# PIC32MZ.net
KiCad netlist of a schematic drawn in Altium Designer
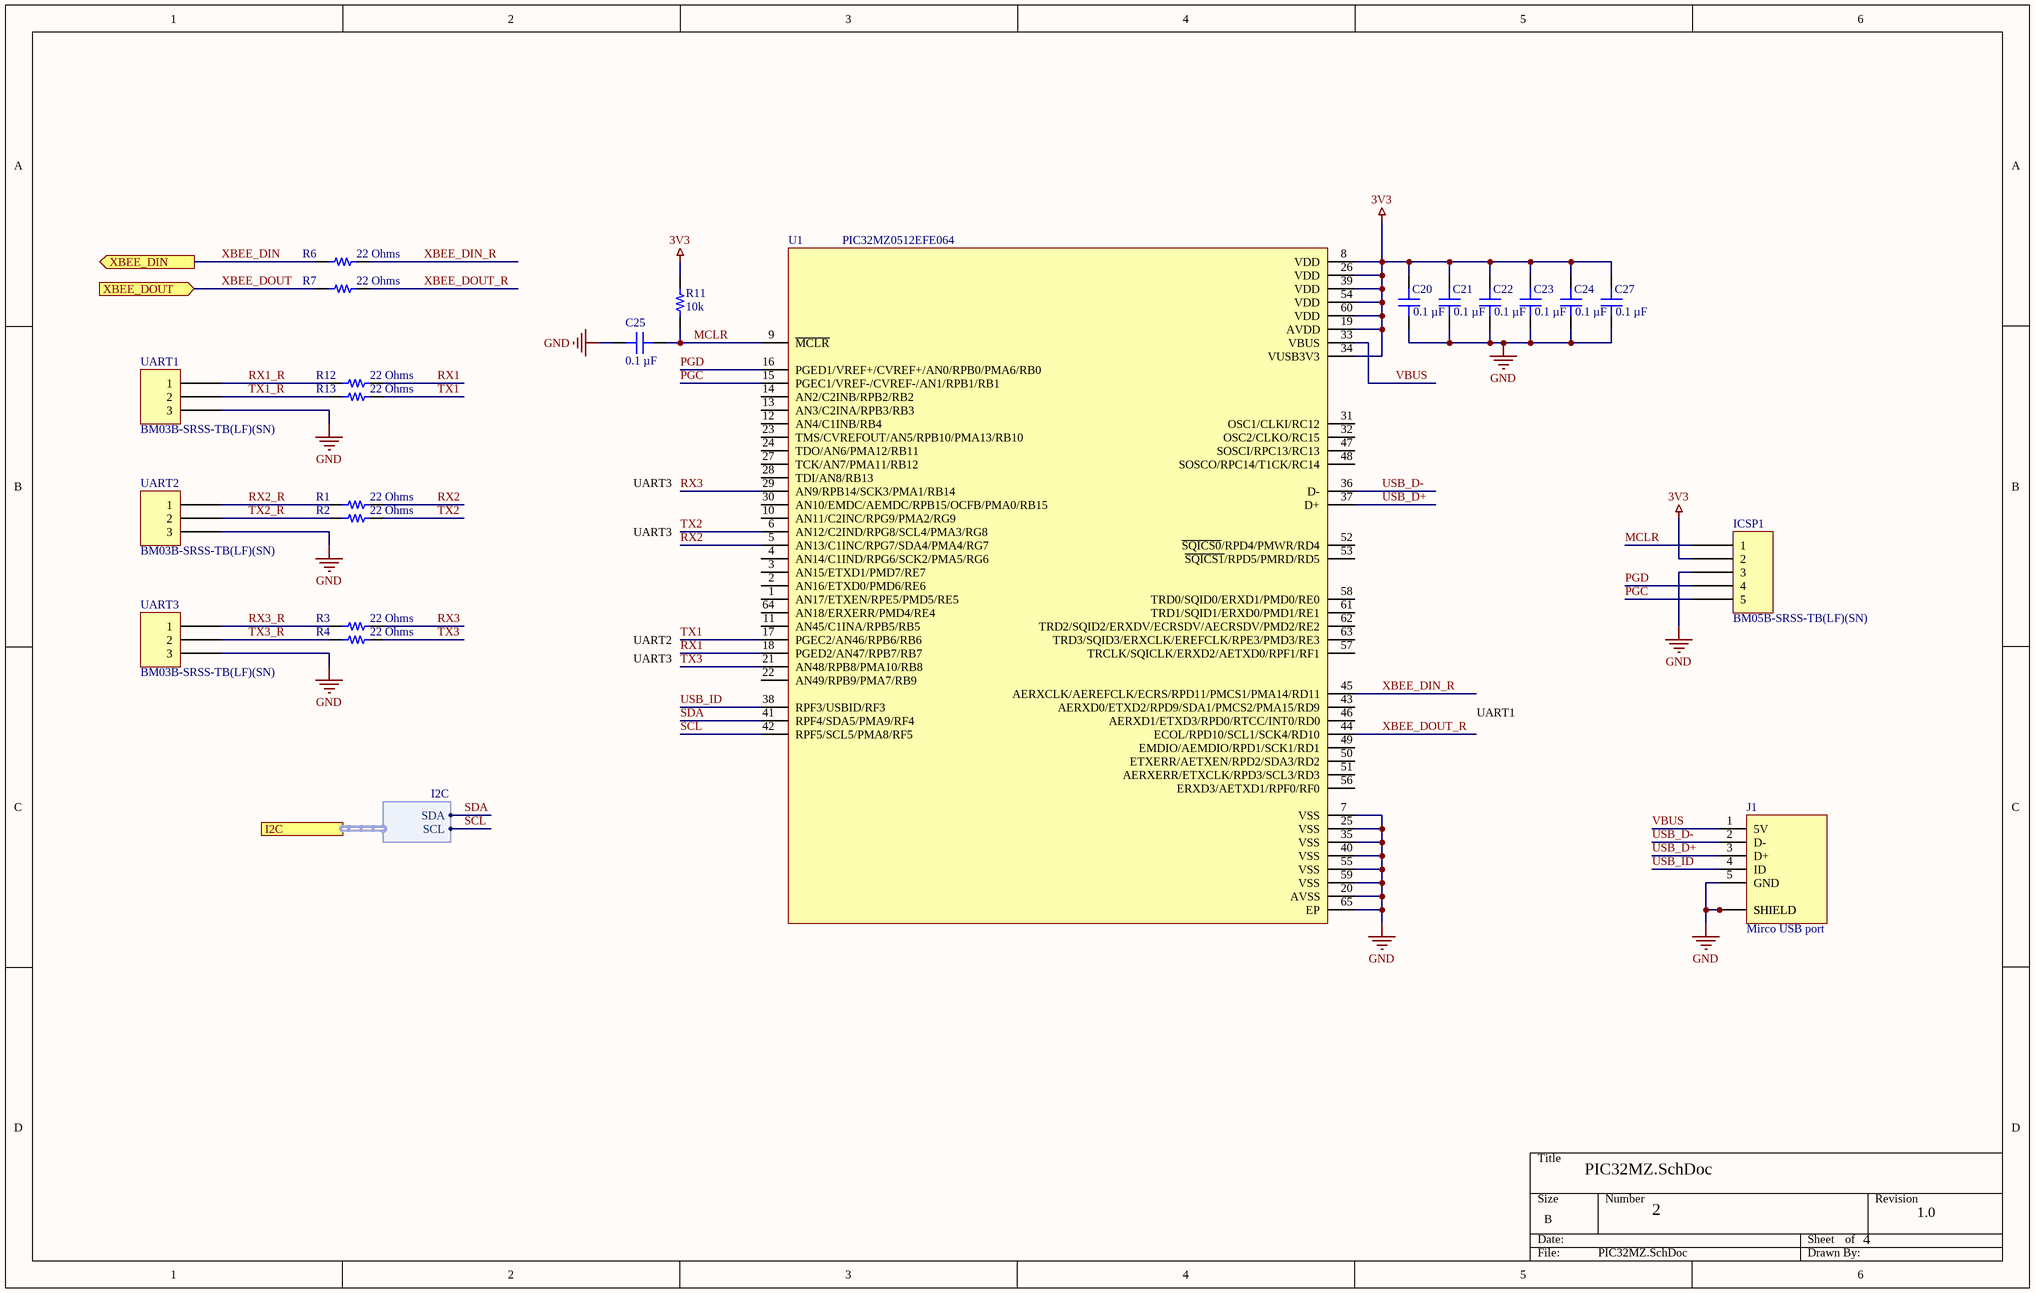
[diagram p0: PIC32MZ.SchDoc]

(export (version "E")
  (design (tool "Eeschema 10.0.6"))
  (components
    (comp (ref "C20")
      (value "0.1 µF")
      (footprint "CAP 0402_1005")
      (description "CAP CER 0.1UF 16V X7R 0402")
      (fields (field (name "PART NUMBER") "C0402C104K4RACAUTO") (field (name "MANUFACTURER") "KEMET"))
      (libsource (lib "Celestial Altium Library - altium_library") (part "Capacitor"))
    )
    (comp (ref "C21")
      (value "0.1 µF")
      (footprint "CAP 0402_1005")
      (description "CAP CER 0.1UF 16V X7R 0402")
      (fields (field (name "PART NUMBER") "C0402C104K4RACAUTO") (field (name "MANUFACTURER") "KEMET"))
      (libsource (lib "Celestial Altium Library - altium_library") (part "Capacitor"))
    )
    (comp (ref "C22")
      (value "0.1 µF")
      (footprint "CAP 0402_1005")
      (description "CAP CER 0.1UF 16V X7R 0402")
      (fields (field (name "PART NUMBER") "C0402C104K4RACAUTO") (field (name "MANUFACTURER") "KEMET"))
      (libsource (lib "Celestial Altium Library - altium_library") (part "Capacitor"))
    )
    (comp (ref "C23")
      (value "0.1 µF")
      (footprint "CAP 0402_1005")
      (description "CAP CER 0.1UF 16V X7R 0402")
      (fields (field (name "PART NUMBER") "C0402C104K4RACAUTO") (field (name "MANUFACTURER") "KEMET"))
      (libsource (lib "Celestial Altium Library - altium_library") (part "Capacitor"))
    )
    (comp (ref "C24")
      (value "0.1 µF")
      (footprint "CAP 0402_1005")
      (description "CAP CER 0.1UF 16V X7R 0402")
      (fields (field (name "PART NUMBER") "C0402C104K4RACAUTO") (field (name "MANUFACTURER") "KEMET"))
      (libsource (lib "Celestial Altium Library - altium_library") (part "Capacitor"))
    )
    (comp (ref "C25")
      (value "0.1 µF")
      (footprint "CAP 0402_1005")
      (description "CAP CER 0.1UF 16V X7R 0402")
      (fields (field (name "PART NUMBER") "C0402C104K4RACAUTO") (field (name "MANUFACTURER") "KEMET"))
      (libsource (lib "Celestial Altium Library - altium_library") (part "Capacitor"))
    )
    (comp (ref "C27")
      (value "0.1 µF")
      (footprint "CAP 0402_1005")
      (description "CAP CER 0.1UF 16V X7R 0402")
      (fields (field (name "PART NUMBER") "C0402C104K4RACAUTO") (field (name "MANUFACTURER") "KEMET"))
      (libsource (lib "Celestial Altium Library - altium_library") (part "Capacitor"))
    )
    (comp (ref "ICSP1")
      (value "BM05B-SRSS-TB(LF)(SN)")
      (footprint "JST BM05B-SRSS-TB")
      (description "CONN HEADER SMD 5POS 1MM")
      (fields (field (name "MANUFACTURER") "JST Sales America Inc."))
      (libsource (lib "Celestial Altium Library - altium_library") (part "5 Pin"))
    )
    (comp (ref "J1")
      (value "Mirco USB port")
      (footprint "AMPHENOL_10118194-0001LF")
      (description "USB - micro B USB 2.0 Receptacle Connector 5 Position Surface Mount, Right Angle; Through Hole")
      (fields (field (name "MF") "Amphenol ICC") (field (name "MP") "10118194-0001LF"))
      (libsource (lib "IC") (part "10118194-0001LF"))
    )
    (comp (ref "R1")
      (value "22 Ohms")
      (footprint "RES 0402_1005")
      (description "RES 14.3K OHM 1% 1/10W 0402")
      (fields
        (field (name "PART NUMBER") "RK73H1ETTP1432F")
        (field (name "MANUFACTURER") "KOA Speer Electronics, Inc.")
      )
      (libsource (lib "Celestial Altium Library - altium_library") (part "Resistor"))
    )
    (comp (ref "R2")
      (value "22 Ohms")
      (footprint "RES 0402_1005")
      (description "RES 14.3K OHM 1% 1/10W 0402")
      (fields
        (field (name "PART NUMBER") "RK73H1ETTP1432F")
        (field (name "MANUFACTURER") "KOA Speer Electronics, Inc.")
      )
      (libsource (lib "Celestial Altium Library - altium_library") (part "Resistor"))
    )
    (comp (ref "R3")
      (value "22 Ohms")
      (footprint "RES 0402_1005")
      (description "RES 14.3K OHM 1% 1/10W 0402")
      (fields
        (field (name "PART NUMBER") "RK73H1ETTP1432F")
        (field (name "MANUFACTURER") "KOA Speer Electronics, Inc.")
      )
      (libsource (lib "Celestial Altium Library - altium_library") (part "Resistor"))
    )
    (comp (ref "R4")
      (value "22 Ohms")
      (footprint "RES 0402_1005")
      (description "RES 14.3K OHM 1% 1/10W 0402")
      (fields
        (field (name "PART NUMBER") "RK73H1ETTP1432F")
        (field (name "MANUFACTURER") "KOA Speer Electronics, Inc.")
      )
      (libsource (lib "Celestial Altium Library - altium_library") (part "Resistor"))
    )
    (comp (ref "R6")
      (value "22 Ohms")
      (footprint "RES 0402_1005")
      (description "RES 14.3K OHM 1% 1/10W 0402")
      (fields
        (field (name "PART NUMBER") "RK73H1ETTP1432F")
        (field (name "MANUFACTURER") "KOA Speer Electronics, Inc.")
      )
      (libsource (lib "Celestial Altium Library - altium_library") (part "Resistor"))
    )
    (comp (ref "R7")
      (value "22 Ohms")
      (footprint "RES 0402_1005")
      (description "RES 14.3K OHM 1% 1/10W 0402")
      (fields
        (field (name "PART NUMBER") "RK73H1ETTP1432F")
        (field (name "MANUFACTURER") "KOA Speer Electronics, Inc.")
      )
      (libsource (lib "Celestial Altium Library - altium_library") (part "Resistor"))
    )
    (comp (ref "R11")
      (value "10k")
      (footprint "RES 0402_1005")
      (description "RES 14.3K OHM 1% 1/10W 0402")
      (fields
        (field (name "PART NUMBER") "RK73H1ETTP1432F")
        (field (name "MANUFACTURER") "KOA Speer Electronics, Inc.")
      )
      (libsource (lib "Celestial Altium Library - altium_library") (part "Resistor"))
    )
    (comp (ref "R12")
      (value "22 Ohms")
      (footprint "RES 0402_1005")
      (description "RES 14.3K OHM 1% 1/10W 0402")
      (fields
        (field (name "PART NUMBER") "RK73H1ETTP1432F")
        (field (name "MANUFACTURER") "KOA Speer Electronics, Inc.")
      )
      (libsource (lib "Celestial Altium Library - altium_library") (part "Resistor"))
    )
    (comp (ref "R13")
      (value "22 Ohms")
      (footprint "RES 0402_1005")
      (description "RES 14.3K OHM 1% 1/10W 0402")
      (fields
        (field (name "PART NUMBER") "RK73H1ETTP1432F")
        (field (name "MANUFACTURER") "KOA Speer Electronics, Inc.")
      )
      (libsource (lib "Celestial Altium Library - altium_library") (part "Resistor"))
    )
    (comp (ref "U1")
      (value "PIC32MZ0512EFE064")
      (footprint "QFN50P900X900X100-65N")
      (description "32-bit Microcontrollers - MCU 32-BIT MCU 512KB FL 128KB RAM, No Crypto")
      (fields (field (name "MF") "Microchip") (field (name "MP") "PIC32MZ2048EFG064T-I/PT"))
      (libsource (lib "IC") (part "PIC32MZ0512EFE064-I/PT"))
    )
    (comp (ref "UART1")
      (value "BM03B-SRSS-TB(LF)(SN)")
      (footprint "JST BM03B-SRSS-TB")
      (description "CONN HEADER SMD 3POS 1MM")
      (fields (field (name "MANUFACTURER") "JST Sales America Inc."))
      (libsource (lib "Celestial Altium Library - altium_library") (part "3 Pin"))
    )
    (comp (ref "UART2")
      (value "BM03B-SRSS-TB(LF)(SN)")
      (footprint "JST BM03B-SRSS-TB")
      (description "CONN HEADER SMD 3POS 1MM")
      (fields (field (name "MANUFACTURER") "JST Sales America Inc."))
      (libsource (lib "Celestial Altium Library - altium_library") (part "3 Pin"))
    )
    (comp (ref "UART3")
      (value "BM03B-SRSS-TB(LF)(SN)")
      (footprint "JST BM03B-SRSS-TB")
      (description "CONN HEADER SMD 3POS 1MM")
      (fields (field (name "MANUFACTURER") "JST Sales America Inc."))
      (libsource (lib "Celestial Altium Library - altium_library") (part "3 Pin"))
    )
  )
  (nets
    (net (code "2") (name "/MCLR") (class "Default")
      (node (ref "C25") (pin "1") (pinfunction "1_1") (pintype "passive"))
      (node (ref "ICSP1") (pin "1") (pinfunction "1_1") (pintype "passive"))
      (node (ref "R11") (pin "2") (pinfunction "2_2") (pintype "passive"))
      (node (ref "U1") (pin "9") (pinfunction "~{MCLR}_9") (pintype "passive"))
    )
    (net (code "3") (name "/PGC") (class "Default")
      (node (ref "ICSP1") (pin "5") (pinfunction "5_5") (pintype "passive"))
      (node (ref "U1") (pin "15") (pinfunction "PGEC1/VREF-/CVREF-/AN1/RPB1/RB1_15") (pintype "passive"))
    )
    (net (code "4") (name "/PGD") (class "Default")
      (node (ref "ICSP1") (pin "4") (pinfunction "4_4") (pintype "passive"))
      (node (ref "U1") (pin "16") (pinfunction "PGED1/VREF+/CVREF+/AN0/RPB0/PMA6/RB0_16") (pintype "passive"))
    )
    (net (code "5") (name "/RX1") (class "Default")
      (node (ref "R12") (pin "1") (pinfunction "1_1") (pintype "passive"))
      (node (ref "U1") (pin "18") (pinfunction "PGED2/AN47/RPB7/RB7_18") (pintype "passive"))
    )
    (net (code "6") (name "/RX1_R") (class "Default")
      (node (ref "R12") (pin "2") (pinfunction "2_2") (pintype "passive"))
      (node (ref "UART1") (pin "1") (pinfunction "1_1") (pintype "passive"))
    )
    (net (code "7") (name "/RX2") (class "Default")
      (node (ref "R1") (pin "1") (pinfunction "1_1") (pintype "passive"))
      (node (ref "U1") (pin "5") (pinfunction "AN13/C1INC/RPG7/SDA4/PMA4/RG7_5") (pintype "passive"))
    )
    (net (code "8") (name "/RX2_R") (class "Default")
      (node (ref "R1") (pin "2") (pinfunction "2_2") (pintype "passive"))
      (node (ref "UART2") (pin "1") (pinfunction "1_1") (pintype "passive"))
    )
    (net (code "9") (name "/RX3") (class "Default")
      (node (ref "R3") (pin "1") (pinfunction "1_1") (pintype "passive"))
      (node (ref "U1") (pin "29") (pinfunction "AN9/RPB14/SCK3/PMA1/RB14_29") (pintype "passive"))
    )
    (net (code "10") (name "/RX3_R") (class "Default")
      (node (ref "R3") (pin "2") (pinfunction "2_2") (pintype "passive"))
      (node (ref "UART3") (pin "1") (pinfunction "1_1") (pintype "passive"))
    )
    (net (code "11") (name "/SCL") (class "Default")
      (node (ref "U1") (pin "42") (pinfunction "RPF5/SCL5/PMA8/RF5_42") (pintype "passive"))
    )
    (net (code "12") (name "/SDA") (class "Default")
      (node (ref "U1") (pin "41") (pinfunction "RPF4/SDA5/PMA9/RF4_41") (pintype "passive"))
    )
    (net (code "13") (name "/TX1") (class "Default")
      (node (ref "R13") (pin "1") (pinfunction "1_1") (pintype "passive"))
      (node (ref "U1") (pin "17") (pinfunction "PGEC2/AN46/RPB6/RB6_17") (pintype "passive"))
    )
    (net (code "14") (name "/TX1_R") (class "Default")
      (node (ref "R13") (pin "2") (pinfunction "2_2") (pintype "passive"))
      (node (ref "UART1") (pin "2") (pinfunction "2_2") (pintype "passive"))
    )
    (net (code "15") (name "/TX2") (class "Default")
      (node (ref "R2") (pin "1") (pinfunction "1_1") (pintype "passive"))
      (node (ref "U1") (pin "6") (pinfunction "AN12/C2IND/RPG8/SCL4/PMA3/RG8_6") (pintype "passive"))
    )
    (net (code "16") (name "/TX2_R") (class "Default")
      (node (ref "R2") (pin "2") (pinfunction "2_2") (pintype "passive"))
      (node (ref "UART2") (pin "2") (pinfunction "2_2") (pintype "passive"))
    )
    (net (code "17") (name "/TX3") (class "Default")
      (node (ref "R4") (pin "1") (pinfunction "1_1") (pintype "passive"))
      (node (ref "U1") (pin "21") (pinfunction "AN48/RPB8/PMA10/RB8_21") (pintype "passive"))
    )
    (net (code "18") (name "/TX3_R") (class "Default")
      (node (ref "R4") (pin "2") (pinfunction "2_2") (pintype "passive"))
      (node (ref "UART3") (pin "2") (pinfunction "2_2") (pintype "passive"))
    )
    (net (code "19") (name "/USB_D+") (class "Default")
      (node (ref "J1") (pin "3") (pinfunction "D+_3") (pintype "passive"))
      (node (ref "U1") (pin "37") (pinfunction "D+_37") (pintype "passive"))
    )
    (net (code "20") (name "/USB_D-") (class "Default")
      (node (ref "J1") (pin "2") (pinfunction "D-_2") (pintype "passive"))
      (node (ref "U1") (pin "36") (pinfunction "D-_36") (pintype "passive"))
    )
    (net (code "21") (name "/USB_ID") (class "Default")
      (node (ref "J1") (pin "4") (pinfunction "ID_4") (pintype "passive"))
      (node (ref "U1") (pin "38") (pinfunction "RPF3/USBID/RF3_38") (pintype "passive"))
    )
    (net (code "22") (name "/VBUS") (class "Default")
      (node (ref "J1") (pin "1") (pinfunction "5V_1") (pintype "passive"))
      (node (ref "U1") (pin "33") (pinfunction "VBUS_33") (pintype "power_in"))
    )
    (net (code "23") (name "/XBEE_DIN") (class "Default")
      (node (ref "R6") (pin "2") (pinfunction "2_2") (pintype "passive"))
    )
    (net (code "24") (name "/XBEE_DIN_R") (class "Default")
      (node (ref "R6") (pin "1") (pinfunction "1_1") (pintype "passive"))
      (node (ref "U1") (pin "45") (pinfunction "AERXCLK/AEREFCLK/ECRS/RPD11/PMCS1/PMA14/RD11_45") (pintype "passive"))
    )
    (net (code "25") (name "/XBEE_DOUT") (class "Default")
      (node (ref "R7") (pin "2") (pinfunction "2_2") (pintype "passive"))
    )
    (net (code "26") (name "/XBEE_DOUT_R") (class "Default")
      (node (ref "R7") (pin "1") (pinfunction "1_1") (pintype "passive"))
      (node (ref "U1") (pin "44") (pinfunction "ECOL/RPD10/SCL1/SCK4/RD10_44") (pintype "passive"))
    )
    (net (code "28") (name "3V3") (class "Default")
      (node (ref "C20") (pin "2") (pinfunction "2_2") (pintype "passive"))
      (node (ref "C21") (pin "2") (pinfunction "2_2") (pintype "passive"))
      (node (ref "C22") (pin "2") (pinfunction "2_2") (pintype "passive"))
      (node (ref "C23") (pin "2") (pinfunction "2_2") (pintype "passive"))
      (node (ref "C24") (pin "2") (pinfunction "2_2") (pintype "passive"))
      (node (ref "C27") (pin "2") (pinfunction "2_2") (pintype "passive"))
      (node (ref "ICSP1") (pin "2") (pinfunction "2_2") (pintype "passive"))
      (node (ref "R11") (pin "1") (pinfunction "1_1") (pintype "passive"))
      (node (ref "U1") (pin "19") (pinfunction "AVDD_19") (pintype "power_in"))
      (node (ref "U1") (pin "26") (pinfunction "VDD_26") (pintype "power_in"))
      (node (ref "U1") (pin "34") (pinfunction "VUSB3V3_34") (pintype "power_in"))
      (node (ref "U1") (pin "39") (pinfunction "VDD_39") (pintype "power_in"))
      (node (ref "U1") (pin "54") (pinfunction "VDD_54") (pintype "power_in"))
      (node (ref "U1") (pin "60") (pinfunction "VDD_60") (pintype "power_in"))
      (node (ref "U1") (pin "8") (pinfunction "VDD_8") (pintype "power_in"))
    )
    (net (code "29") (name "GND") (class "Default")
      (node (ref "C20") (pin "1") (pinfunction "1_1") (pintype "passive"))
      (node (ref "C21") (pin "1") (pinfunction "1_1") (pintype "passive"))
      (node (ref "C22") (pin "1") (pinfunction "1_1") (pintype "passive"))
      (node (ref "C23") (pin "1") (pinfunction "1_1") (pintype "passive"))
      (node (ref "C24") (pin "1") (pinfunction "1_1") (pintype "passive"))
      (node (ref "C25") (pin "2") (pinfunction "2_2") (pintype "passive"))
      (node (ref "C27") (pin "1") (pinfunction "1_1") (pintype "passive"))
      (node (ref "ICSP1") (pin "3") (pinfunction "3_3") (pintype "passive"))
      (node (ref "J1") (pin "5") (pinfunction "GND_5") (pintype "passive"))
      (node (ref "J1") (pin "S1") (pinfunction "SHIELD_S1") (pintype "passive"))
      (node (ref "J1") (pin "S2") (pinfunction "SHIELD_S2") (pintype "passive"))
      (node (ref "J1") (pin "S3") (pinfunction "SHIELD_S3") (pintype "passive"))
      (node (ref "J1") (pin "S4") (pinfunction "SHIELD_S4") (pintype "passive"))
      (node (ref "J1") (pin "S5") (pinfunction "SHIELD_S5") (pintype "passive"))
      (node (ref "J1") (pin "S6") (pinfunction "SHIELD_S6") (pintype "passive"))
      (node (ref "U1") (pin "20") (pinfunction "AVSS_20") (pintype "power_in"))
      (node (ref "U1") (pin "25") (pinfunction "VSS_25") (pintype "power_in"))
      (node (ref "U1") (pin "35") (pinfunction "VSS_35") (pintype "power_in"))
      (node (ref "U1") (pin "40") (pinfunction "VSS_40") (pintype "power_in"))
      (node (ref "U1") (pin "55") (pinfunction "VSS_55") (pintype "power_in"))
      (node (ref "U1") (pin "59") (pinfunction "VSS_59") (pintype "power_in"))
      (node (ref "U1") (pin "65") (pinfunction "EP_65") (pintype "power_in"))
      (node (ref "U1") (pin "7") (pinfunction "VSS_7") (pintype "power_in"))
      (node (ref "UART1") (pin "3") (pinfunction "3_3") (pintype "passive"))
      (node (ref "UART2") (pin "3") (pinfunction "3_3") (pintype "passive"))
      (node (ref "UART3") (pin "3") (pinfunction "3_3") (pintype "passive"))
    )
    (net (code "30") (name "unconnected-(U1-AERXD0{slash}ETXD2{slash}RPD9{slash}SDA1{slash}PMCS2{slash}PMA15{slash}RD9-Pad43)") (class "Default")
      (node (ref "U1") (pin "43") (pinfunction "AERXD0/ETXD2/RPD9/SDA1/PMCS2/PMA15/RD9_43") (pintype "passive"))
    )
    (net (code "31") (name "unconnected-(U1-AERXD1{slash}ETXD3{slash}RPD0{slash}RTCC{slash}INT0{slash}RD0-Pad46)") (class "Default")
      (node (ref "U1") (pin "46") (pinfunction "AERXD1/ETXD3/RPD0/RTCC/INT0/RD0_46") (pintype "passive"))
    )
    (net (code "32") (name "unconnected-(U1-AERXERR{slash}ETXCLK{slash}RPD3{slash}SCL3{slash}RD3-Pad51)") (class "Default")
      (node (ref "U1") (pin "51") (pinfunction "AERXERR/ETXCLK/RPD3/SCL3/RD3_51") (pintype "passive"))
    )
    (net (code "33") (name "unconnected-(U1-AN2{slash}C2INB{slash}RPB2{slash}RB2-Pad14)") (class "Default")
      (node (ref "U1") (pin "14") (pinfunction "AN2/C2INB/RPB2/RB2_14") (pintype "passive"))
    )
    (net (code "34") (name "unconnected-(U1-AN3{slash}C2INA{slash}RPB3{slash}RB3-Pad13)") (class "Default")
      (node (ref "U1") (pin "13") (pinfunction "AN3/C2INA/RPB3/RB3_13") (pintype "passive"))
    )
    (net (code "35") (name "unconnected-(U1-AN4{slash}C1INB{slash}RB4-Pad12)") (class "Default")
      (node (ref "U1") (pin "12") (pinfunction "AN4/C1INB/RB4_12") (pintype "passive"))
    )
    (net (code "36") (name "unconnected-(U1-AN10{slash}EMDC{slash}AEMDC{slash}RPB15{slash}OCFB{slash}PMA0{slash}RB15-Pad30)") (class "Default")
      (node (ref "U1") (pin "30") (pinfunction "AN10/EMDC/AEMDC/RPB15/OCFB/PMA0/RB15_30") (pintype "passive"))
    )
    (net (code "37") (name "unconnected-(U1-AN11{slash}C2INC{slash}RPG9{slash}PMA2{slash}RG9-Pad10)") (class "Default")
      (node (ref "U1") (pin "10") (pinfunction "AN11/C2INC/RPG9/PMA2/RG9_10") (pintype "passive"))
    )
    (net (code "38") (name "unconnected-(U1-AN14{slash}C1IND{slash}RPG6{slash}SCK2{slash}PMA5{slash}RG6-Pad4)") (class "Default")
      (node (ref "U1") (pin "4") (pinfunction "AN14/C1IND/RPG6/SCK2/PMA5/RG6_4") (pintype "passive"))
    )
    (net (code "39") (name "unconnected-(U1-AN15{slash}ETXD1{slash}PMD7{slash}RE7-Pad3)") (class "Default")
      (node (ref "U1") (pin "3") (pinfunction "AN15/ETXD1/PMD7/RE7_3") (pintype "passive"))
    )
    (net (code "40") (name "unconnected-(U1-AN16{slash}ETXD0{slash}PMD6{slash}RE6-Pad2)") (class "Default")
      (node (ref "U1") (pin "2") (pinfunction "AN16/ETXD0/PMD6/RE6_2") (pintype "passive"))
    )
    (net (code "41") (name "unconnected-(U1-AN17{slash}ETXEN{slash}RPE5{slash}PMD5{slash}RE5-Pad1)") (class "Default")
      (node (ref "U1") (pin "1") (pinfunction "AN17/ETXEN/RPE5/PMD5/RE5_1") (pintype "passive"))
    )
    (net (code "42") (name "unconnected-(U1-AN18{slash}ERXERR{slash}PMD4{slash}RE4-Pad64)") (class "Default")
      (node (ref "U1") (pin "64") (pinfunction "AN18/ERXERR/PMD4/RE4_64") (pintype "passive"))
    )
    (net (code "43") (name "unconnected-(U1-AN45{slash}C1INA{slash}RPB5{slash}RB5-Pad11)") (class "Default")
      (node (ref "U1") (pin "11") (pinfunction "AN45/C1INA/RPB5/RB5_11") (pintype "passive"))
    )
    (net (code "44") (name "unconnected-(U1-AN49{slash}RPB9{slash}PMA7{slash}RB9-Pad22)") (class "Default")
      (node (ref "U1") (pin "22") (pinfunction "AN49/RPB9/PMA7/RB9_22") (pintype "passive"))
    )
    (net (code "45") (name "unconnected-(U1-EMDIO{slash}AEMDIO{slash}RPD1{slash}SCK1{slash}RD1-Pad49)") (class "Default")
      (node (ref "U1") (pin "49") (pinfunction "EMDIO/AEMDIO/RPD1/SCK1/RD1_49") (pintype "passive"))
    )
    (net (code "46") (name "unconnected-(U1-ERXD3{slash}AETXD1{slash}RPF0{slash}RF0-Pad56)") (class "Default")
      (node (ref "U1") (pin "56") (pinfunction "ERXD3/AETXD1/RPF0/RF0_56") (pintype "passive"))
    )
    (net (code "47") (name "unconnected-(U1-ETXERR{slash}AETXEN{slash}RPD2{slash}SDA3{slash}RD2-Pad50)") (class "Default")
      (node (ref "U1") (pin "50") (pinfunction "ETXERR/AETXEN/RPD2/SDA3/RD2_50") (pintype "passive"))
    )
    (net (code "48") (name "unconnected-(U1-OSC1{slash}CLKI{slash}RC12-Pad31)") (class "Default")
      (node (ref "U1") (pin "31") (pinfunction "OSC1/CLKI/RC12_31") (pintype "passive"))
    )
    (net (code "49") (name "unconnected-(U1-OSC2{slash}CLKO{slash}RC15-Pad32)") (class "Default")
      (node (ref "U1") (pin "32") (pinfunction "OSC2/CLKO/RC15_32") (pintype "passive"))
    )
    (net (code "50") (name "unconnected-(U1-SOSCI{slash}RPC13{slash}RC13-Pad47)") (class "Default")
      (node (ref "U1") (pin "47") (pinfunction "SOSCI/RPC13/RC13_47") (pintype "passive"))
    )
    (net (code "51") (name "unconnected-(U1-SOSCO{slash}RPC14{slash}T1CK{slash}RC14-Pad48)") (class "Default")
      (node (ref "U1") (pin "48") (pinfunction "SOSCO/RPC14/T1CK/RC14_48") (pintype "passive"))
    )
    (net (code "52") (name "unconnected-(U1-TCK{slash}AN7{slash}PMA11{slash}RB12-Pad27)") (class "Default")
      (node (ref "U1") (pin "27") (pinfunction "TCK/AN7/PMA11/RB12_27") (pintype "passive"))
    )
    (net (code "53") (name "unconnected-(U1-TDI{slash}AN8{slash}RB13-Pad28)") (class "Default")
      (node (ref "U1") (pin "28") (pinfunction "TDI/AN8/RB13_28") (pintype "passive"))
    )
    (net (code "54") (name "unconnected-(U1-TDO{slash}AN6{slash}PMA12{slash}RB11-Pad24)") (class "Default")
      (node (ref "U1") (pin "24") (pinfunction "TDO/AN6/PMA12/RB11_24") (pintype "passive"))
    )
    (net (code "55") (name "unconnected-(U1-TMS{slash}CVREFOUT{slash}AN5{slash}RPB10{slash}PMA13{slash}RB10-Pad23)") (class "Default")
      (node (ref "U1") (pin "23") (pinfunction "TMS/CVREFOUT/AN5/RPB10/PMA13/RB10_23") (pintype "passive"))
    )
    (net (code "56") (name "unconnected-(U1-TRCLK{slash}SQICLK{slash}ERXD2{slash}AETXD0{slash}RPF1{slash}RF1-Pad57)") (class "Default")
      (node (ref "U1") (pin "57") (pinfunction "TRCLK/SQICLK/ERXD2/AETXD0/RPF1/RF1_57") (pintype "passive"))
    )
    (net (code "57") (name "unconnected-(U1-TRD0{slash}SQID0{slash}ERXD1{slash}PMD0{slash}RE0-Pad58)") (class "Default")
      (node (ref "U1") (pin "58") (pinfunction "TRD0/SQID0/ERXD1/PMD0/RE0_58") (pintype "passive"))
    )
    (net (code "58") (name "unconnected-(U1-TRD1{slash}SQID1{slash}ERXD0{slash}PMD1{slash}RE1-Pad61)") (class "Default")
      (node (ref "U1") (pin "61") (pinfunction "TRD1/SQID1/ERXD0/PMD1/RE1_61") (pintype "passive"))
    )
    (net (code "59") (name "unconnected-(U1-TRD2{slash}SQID2{slash}ERXDV{slash}ECRSDV{slash}AECRSDV{slash}PMD2{slash}RE2-Pad62)") (class "Default")
      (node (ref "U1") (pin "62") (pinfunction "TRD2/SQID2/ERXDV/ECRSDV/AECRSDV/PMD2/RE2_62") (pintype "passive"))
    )
    (net (code "60") (name "unconnected-(U1-TRD3{slash}SQID3{slash}ERXCLK{slash}EREFCLK{slash}RPE3{slash}PMD3{slash}RE3-Pad63)") (class "Default")
      (node (ref "U1") (pin "63") (pinfunction "TRD3/SQID3/ERXCLK/EREFCLK/RPE3/PMD3/RE3_63") (pintype "passive"))
    )
    (net (code "61") (name "unconnected-(U1-~{SQICS0}{slash}RPD4{slash}PMWR{slash}RD4-Pad52)") (class "Default")
      (node (ref "U1") (pin "52") (pinfunction "~{SQICS0}/RPD4/PMWR/RD4_52") (pintype "passive"))
    )
    (net (code "62") (name "unconnected-(U1-~{SQICS1}{slash}RPD5{slash}PMRD{slash}RD5-Pad53)") (class "Default")
      (node (ref "U1") (pin "53") (pinfunction "~{SQICS1}/RPD5/PMRD/RD5_53") (pintype "passive"))
    )
  )
)
